# BMS.net
KiCad netlist of a schematic drawn in Altium Designer
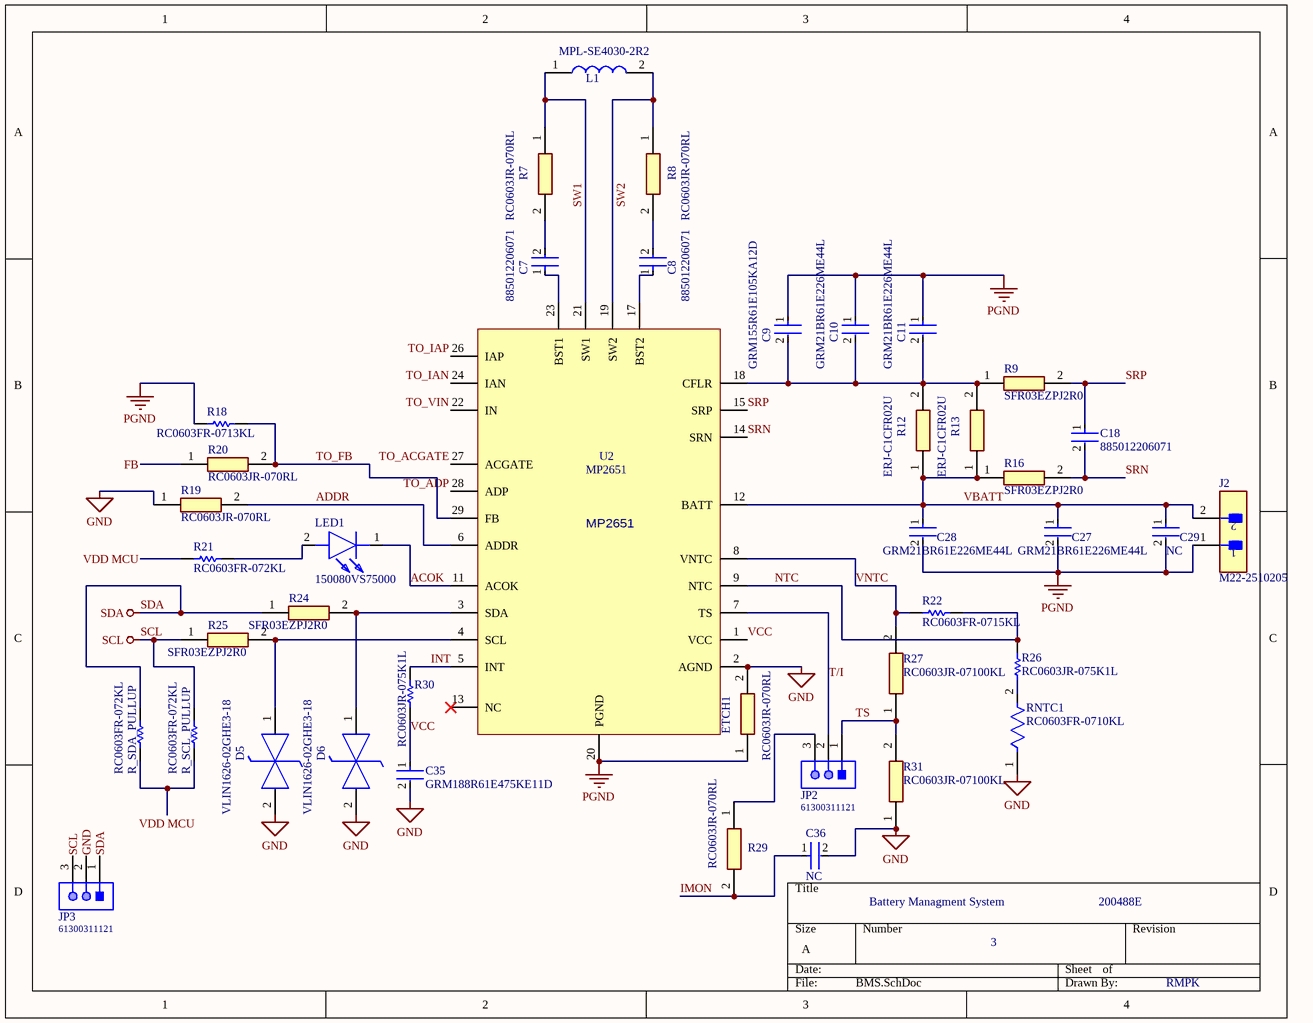
[diagram p0: BMS.SchDoc]

(export (version "E")
  (design (tool "Eeschema 10.0.6"))
  (components
    (comp (ref "C7")
      (value "885012206071")
      (footprint "FP-885012206071-MFG")
      (description "CAP CER 0.1UF 25V X7R 0603")
      (fields (field (name "TOLERANCE") "10%"))
      (libsource (lib "Altium Content Vault") (part "11868f565c42a9108669ba33697ecf6"))
    )
    (comp (ref "C8")
      (value "885012206071")
      (footprint "FP-885012206071-MFG")
      (description "CAP CER 0.1UF 25V X7R 0603")
      (fields (field (name "TOLERANCE") "10%"))
      (libsource (lib "Altium Content Vault") (part "11868f565c42a9108669ba33697ecf6"))
    )
    (comp (ref "C9")
      (value "GRM155R61E105KA12D")
      (footprint "FP-GRM155-0_05-IPC_B")
      (description "Chip Multilayer Ceramic Capacitors for General Purpose, 0402, 1.0uF, X5R, 15%, 10%, 25V")
      (fields (field (name "VOLTAGE") "25V") (field (name "TOLERANCE") "10%"))
      (libsource (lib "Altium Content Vault") (part "02cd4be3c70576c341d710602a673aa"))
    )
    (comp (ref "C10")
      (value "GRM21BR61E226ME44L")
      (footprint "FP-GRM21B-0_2-e0_2_0_7-IPC_B")
      (description "Chip Multilayer Ceramic Capacitors for General Purpose, 0805, 22uF, X5R, 15%, 20%, 25V")
      (fields (field (name "TOLERANCE") "20%") (field (name "VOLTAGE") "25V"))
      (libsource (lib "Altium Content Vault") (part "b4654b650e69147ec39a6b967a45e02"))
    )
    (comp (ref "C11")
      (value "GRM21BR61E226ME44L")
      (footprint "FP-GRM21B-0_2-e0_2_0_7-IPC_B")
      (description "Chip Multilayer Ceramic Capacitors for General Purpose, 0805, 22uF, X5R, 15%, 20%, 25V")
      (fields (field (name "TOLERANCE") "20%") (field (name "VOLTAGE") "25V"))
      (libsource (lib "Altium Content Vault") (part "b4654b650e69147ec39a6b967a45e02"))
    )
    (comp (ref "C18")
      (value "885012206071")
      (footprint "FP-885012206071-MFG")
      (description "CAP CER 0.1UF 25V X7R 0603")
      (fields (field (name "TOLERANCE") "10%"))
      (libsource (lib "Altium Content Vault") (part "11868f565c42a9108669ba33697ecf6"))
    )
    (comp (ref "C27")
      (value "GRM21BR61E226ME44L")
      (footprint "FP-GRM21B-0_2-e0_2_0_7-IPC_B")
      (description "Chip Multilayer Ceramic Capacitors for General Purpose, 0805, 22uF, X5R, 15%, 20%, 25V")
      (fields (field (name "TOLERANCE") "20%") (field (name "VOLTAGE") "25V"))
      (libsource (lib "Altium Content Vault") (part "b4654b650e69147ec39a6b967a45e02"))
    )
    (comp (ref "C28")
      (value "GRM21BR61E226ME44L")
      (footprint "FP-GRM21B-0_2-e0_2_0_7-IPC_B")
      (description "Chip Multilayer Ceramic Capacitors for General Purpose, 0805, 22uF, X5R, 15%, 20%, 25V")
      (fields (field (name "TOLERANCE") "20%") (field (name "VOLTAGE") "25V"))
      (libsource (lib "Altium Content Vault") (part "b4654b650e69147ec39a6b967a45e02"))
    )
    (comp (ref "C29")
      (value "NC")
      (footprint "FP-GRM21B-0_2-e0_2_0_7-IPC_B")
      (description "Chip Multilayer Ceramic Capacitors for General Purpose, 0805, 22uF, X5R, 15%, 20%, 25V")
      (fields (field (name "TOLERANCE") "20%") (field (name "VOLTAGE") "25V"))
      (libsource (lib "Altium Content Vault") (part "b4654b650e69147ec39a6b967a45e02"))
    )
    (comp (ref "C35")
      (value "GRM188R61E475KE11D")
      (footprint "FP-GRM188-0_15-IPC_C")
      (description "Chip Multilayer Ceramic Capacitors for General Purpose, 0603, 4.7uF, X5R, 15%, 10%, 25V")
      (fields (field (name "VOLTAGE") "25V") (field (name "TOLERANCE") "10%"))
      (libsource (lib "Altium Content Vault") (part "02cd4be3c70576c341d710602a673aa"))
    )
    (comp (ref "C36")
      (value "NC")
      (footprint "FP-GRM21B-0_2-e0_2_0_7-IPC_B")
      (description "Chip Multilayer Ceramic Capacitors for General Purpose, 0805, 22uF, X5R, 15%, 20%, 25V")
      (fields (field (name "TOLERANCE") "20%") (field (name "VOLTAGE") "25V"))
      (libsource (lib "Altium Content Vault") (part "b4654b650e69147ec39a6b967a45e02"))
    )
    (comp (ref "D5")
      (value "VLIN1626-02GHE3-18")
      (footprint "SamacSys:SOD2713X115N")
      (description "Diode ESD (Bi-directional)")
      (fields (field (name "MOUSER PART NUMBER") "78-VLIN1626-02GHE318"))
      (libsource (lib "*") (part "VLIN1626-02GHE3-18"))
    )
    (comp (ref "D6")
      (value "VLIN1626-02GHE3-18")
      (footprint "SamacSys:SOD2713X115N")
      (description "Diode ESD (Bi-directional)")
      (fields (field (name "MOUSER PART NUMBER") "78-VLIN1626-02GHE318"))
      (libsource (lib "*") (part "VLIN1626-02GHE3-18"))
    )
    (comp (ref "ETCH1")
      (value "RC0603JR-070RL")
      (footprint "SamacSys:RESC1608X55N")
      (description "Resistor")
      (fields (field (name "MOUSER PART NUMBER") "603-RC0603JR-070RL"))
      (libsource (lib "") (part "RC0603JR-070RL_1"))
    )
    (comp (ref "J2")
      (value "M22-2510205")
      (footprint "FP-M22-2510205-MFG")
      (description "CONN HEADER VERT 2POS 2MM")
      (fields
        (field (name "MANUFACTURER") "Harwin")
        (field (name "OCTOPART") "https://octopart.com/m22-2510205-harwin-2538221")
      )
      (libsource (lib "Altium Content Vault") (part "3bc925449376181038e59eaffc5286c"))
    )
    (comp (ref "JP2")
      (value "61300311121")
      (footprint "61300311121")
      (description "THT Vertical Pin Header WR-PHD, Pitch 2.54 mm, Single Row, 3 pins")
      (fields (field (name "MANUFACTURER") "Wurth Elektronik") (field (name "PUBLISHER") "WurthElektronik"))
      (libsource (lib "Altium Content Vault") (part "WE-CN-1P-M-R3"))
    )
    (comp (ref "JP3")
      (value "61300311121")
      (footprint "61300311121")
      (description "THT Vertical Pin Header WR-PHD, Pitch 2.54 mm, Single Row, 3 pins")
      (fields (field (name "MANUFACTURER") "Wurth Elektronik") (field (name "PUBLISHER") "WurthElektronik"))
      (libsource (lib "Altium Content Vault") (part "WE-CN-1P-M-R3"))
    )
    (comp (ref "L1")
      (value "MPL-SE4030-2R2")
      (footprint "SamacSys:MPLSE40302R2")
      (description "Inductor")
      (fields (field (name "MOUSER PART NUMBER") "946-MPL-SE4030-2R2"))
      (libsource (lib "*") (part "MPL-SE4030-2R2"))
    )
    (comp (ref "LED1")
      (value "150080VS75000")
      (footprint "SamacSys:LEDC2012X80N")
      (description "LED")
      (fields (field (name "MOUSER PART NUMBER") "710-150080VS75000"))
      (libsource (lib "*") (part "150080VS75000"))
    )
    (comp (ref "R7")
      (value "RC0603JR-070RL")
      (footprint "SamacSys:RESC1608X55N")
      (description "Resistor")
      (fields (field (name "MOUSER PART NUMBER") "603-RC0603JR-070RL"))
      (libsource (lib "*") (part "RC0603JR-070RL"))
    )
    (comp (ref "R8")
      (value "RC0603JR-070RL")
      (footprint "SamacSys:RESC1608X55N")
      (description "Resistor")
      (fields (field (name "MOUSER PART NUMBER") "603-RC0603JR-070RL"))
      (libsource (lib "*") (part "RC0603JR-070RL"))
    )
    (comp (ref "R9")
      (value "SFR03EZPJ2R0")
      (footprint "SamacSys:RESC1608X55N")
      (description "Resistor")
      (libsource (lib "*") (part "SFR03EZPJ2R0"))
    )
    (comp (ref "R12")
      (value "ERJ-C1CFR02U")
      (footprint "SamacSys:ERJC1")
      (description "Resistor")
      (fields (field (name "MOUSER PART NUMBER") "667-ERJ-C1CFR02U"))
      (libsource (lib "*") (part "ERJ-C1CFR02U"))
    )
    (comp (ref "R13")
      (value "ERJ-C1CFR02U")
      (footprint "SamacSys:ERJC1")
      (description "Resistor")
      (fields (field (name "MOUSER PART NUMBER") "667-ERJ-C1CFR02U"))
      (libsource (lib "*") (part "ERJ-C1CFR02U"))
    )
    (comp (ref "R16")
      (value "SFR03EZPJ2R0")
      (footprint "SamacSys:RESC1608X55N")
      (description "Resistor")
      (libsource (lib "*") (part "SFR03EZPJ2R0"))
    )
    (comp (ref "R18")
      (value "RC0603FR-0713KL")
      (footprint "RESC1608X55X25LL10T15")
      (description "Chip Resistor, 13 KOhm, +/- 1%, 0.1 W, -55 to 155 degC, 0603 (1608 Metric), RoHS, Tape and Reel")
      (fields (field (name "TOLERANCE") "1%") (field (name "MANUFACTURER") "Yageo"))
      (libsource (lib "Altium Content Vault") (part "RES-2"))
    )
    (comp (ref "R19")
      (value "RC0603JR-070RL")
      (footprint "SamacSys:RESC1608X55N")
      (description "Resistor")
      (fields (field (name "MOUSER PART NUMBER") "603-RC0603JR-070RL"))
      (libsource (lib "") (part "RC0603JR-070RL_2"))
    )
    (comp (ref "R20")
      (value "RC0603JR-070RL")
      (footprint "SamacSys:RESC1608X55N")
      (description "Resistor")
      (fields (field (name "MOUSER PART NUMBER") "603-RC0603JR-070RL"))
      (libsource (lib "") (part "RC0603JR-070RL_2"))
    )
    (comp (ref "R21")
      (value "RC0603FR-072KL")
      (footprint "RESC1608X55X25LL10T15")
      (description "Chip Resistor, 2 KOhm, +/- 1%, 50 V, -55 to 155 degC, 0603 (1608 Metric), RoHS, Tape and Reel")
      (fields (field (name "TOLERANCE") "±1%") (field (name "MANUFACTURER") "Yageo"))
      (libsource (lib "Altium Content Vault") (part "RES-2"))
    )
    (comp (ref "R22")
      (value "RC0603FR-0715KL")
      (footprint "RESC1608X55X25LL10T15")
      (description "Chip Resistor, 15 KOhm, +/- 1%, 0.1 W, -55 to 155 degC, 0603 (1608 Metric), RoHS, Tape and Reel")
      (libsource (lib "Altium Content Vault") (part "RES-2"))
    )
    (comp (ref "R24")
      (value "SFR03EZPJ2R0")
      (footprint "SamacSys:RESC1608X55N")
      (description "Resistor")
      (libsource (lib "*") (part "SFR03EZPJ2R0"))
    )
    (comp (ref "R25")
      (value "SFR03EZPJ2R0")
      (footprint "SamacSys:RESC1608X55N")
      (description "Resistor")
      (libsource (lib "*") (part "SFR03EZPJ2R0"))
    )
    (comp (ref "R26")
      (value "RC0603JR-075K1L")
      (footprint "RESC1608X55X25LL10T15")
      (description "Chip Resistor, 5.1 KOhm, +/- 5%, 0.1 W, -55 to 155 degC, 0603 (1608 Metric), RoHS, Tape and Reel")
      (fields (field (name "TOLERANCE") "5%") (field (name "MANUFACTURER") "Yageo"))
      (libsource (lib "Altium Content Vault") (part "RES-2"))
    )
    (comp (ref "R27")
      (value "RC0603JR-07100KL")
      (footprint "SamacSys:RESC1608X55N")
      (description "Resistor")
      (fields (field (name "MOUSER PART NUMBER") "603-RC0603JR-07100KL"))
      (libsource (lib "*") (part "RC0603JR-07100KL"))
    )
    (comp (ref "R29")
      (value "RC0603JR-070RL")
      (footprint "SamacSys:RESC1608X55N")
      (description "Resistor")
      (fields (field (name "MOUSER PART NUMBER") "603-RC0603JR-070RL"))
      (libsource (lib "*") (part "RC0603JR-070RL"))
    )
    (comp (ref "R30")
      (value "RC0603JR-075K1L")
      (footprint "RESC1608X55X25LL10T15")
      (description "Chip Resistor, 5.1 KOhm, +/- 5%, 0.1 W, -55 to 155 degC, 0603 (1608 Metric), RoHS, Tape and Reel")
      (fields (field (name "TOLERANCE") "5%") (field (name "MANUFACTURER") "Yageo"))
      (libsource (lib "Altium Content Vault") (part "RES-2"))
    )
    (comp (ref "R31")
      (value "RC0603JR-07100KL")
      (footprint "SamacSys:RESC1608X55N")
      (description "Resistor")
      (fields (field (name "MOUSER PART NUMBER") "603-RC0603JR-07100KL"))
      (libsource (lib "*") (part "RC0603JR-07100KL"))
    )
    (comp (ref "RNTC1")
      (value "RC0603FR-0710KL")
      (footprint "FP-RC0603-0_55-IPC_C")
      (description "RES 10K OHM 1% 1/10W 0603")
      (fields (field (name "TOLERANCE") "1%"))
      (libsource (lib "Altium Content Vault") (part "1029c3af85768c4190bb7ad29bc67b5"))
    )
    (comp (ref "R_SCL_PULLUP")
      (value "RC0603FR-072KL")
      (footprint "RESC1608X55X25LL10T15")
      (description "Chip Resistor, 2 KOhm, +/- 1%, 50 V, -55 to 155 degC, 0603 (1608 Metric), RoHS, Tape and Reel")
      (fields (field (name "TOLERANCE") "±1%") (field (name "MANUFACTURER") "Yageo"))
      (libsource (lib "Altium Content Vault") (part "RES-2"))
    )
    (comp (ref "R_SDA_PULLUP")
      (value "RC0603FR-072KL")
      (footprint "RESC1608X55X25LL10T15")
      (description "Chip Resistor, 2 KOhm, +/- 1%, 50 V, -55 to 155 degC, 0603 (1608 Metric), RoHS, Tape and Reel")
      (fields (field (name "TOLERANCE") "±1%") (field (name "MANUFACTURER") "Yageo"))
      (libsource (lib "Altium Content Vault") (part "RES-2"))
    )
    (comp (ref "U2")
      (value "MP2651")
      (footprint "MP2651")
      (description "MP2651 – BUCK-BOOST CHARGER FOR 1 TO 4 CELLS IN SERIES")
      (libsource (lib "Schlib1") (part "MP2651"))
    )
  )
  (nets
    (net (code "1") (name "/ACOK") (class "Default")
      (node (ref "LED1") (pin "1") (pinfunction "K_1") (pintype "passive"))
      (node (ref "U2") (pin "11") (pinfunction "ACOK_11") (pintype "passive"))
    )
    (net (code "2") (name "/ADDR") (class "Default")
      (node (ref "R19") (pin "2") (pinfunction "2_2") (pintype "passive"))
      (node (ref "U2") (pin "6") (pinfunction "ADDR_6") (pintype "passive"))
    )
    (net (code "3") (name "/FB") (class "Default")
      (node (ref "R20") (pin "1") (pinfunction "1_1") (pintype "passive"))
    )
    (net (code "4") (name "/IMON") (class "Default")
      (node (ref "C36") (pin "1") (pinfunction "1_1") (pintype "passive"))
      (node (ref "R29") (pin "2") (pinfunction "2_2") (pintype "passive"))
    )
    (net (code "5") (name "/INT") (class "Default")
      (node (ref "R30") (pin "2") (pinfunction "2_2") (pintype "passive"))
      (node (ref "U2") (pin "5") (pinfunction "INT_5") (pintype "passive"))
    )
    (net (code "6") (name "/NTC") (class "Default")
      (node (ref "R22") (pin "2") (pinfunction "2_2") (pintype "passive"))
      (node (ref "R26") (pin "2") (pinfunction "2_2") (pintype "passive"))
      (node (ref "U2") (pin "9") (pinfunction "NTC_9") (pintype "passive"))
    )
    (net (code "7") (name "/SRN") (class "Default")
      (node (ref "C18") (pin "2") (pinfunction "2_2") (pintype "passive"))
      (node (ref "R16") (pin "2") (pinfunction "2_2") (pintype "passive"))
      (node (ref "U2") (pin "14") (pinfunction "SRN_14") (pintype "passive"))
    )
    (net (code "8") (name "/SRP") (class "Default")
      (node (ref "C18") (pin "1") (pinfunction "1_1") (pintype "passive"))
      (node (ref "R9") (pin "2") (pinfunction "2_2") (pintype "passive"))
      (node (ref "U2") (pin "15") (pinfunction "SRP_15") (pintype "passive"))
    )
    (net (code "9") (name "/SW1") (class "Default")
      (node (ref "L1") (pin "1") (pinfunction "1_1") (pintype "passive"))
      (node (ref "R7") (pin "1") (pinfunction "1_1") (pintype "passive"))
      (node (ref "U2") (pin "21") (pinfunction "SW1_21") (pintype "passive"))
    )
    (net (code "10") (name "/SW2") (class "Default")
      (node (ref "L1") (pin "2") (pinfunction "2_2") (pintype "passive"))
      (node (ref "R8") (pin "1") (pinfunction "1_1") (pintype "passive"))
      (node (ref "U2") (pin "19") (pinfunction "SW2_19") (pintype "passive"))
    )
    (net (code "11") (name "/TO_ACGATE") (class "Default")
      (node (ref "U2") (pin "27") (pinfunction "ACGATE_27") (pintype "passive"))
    )
    (net (code "12") (name "/TO_ADP") (class "Default")
      (node (ref "U2") (pin "28") (pinfunction "ADP_28") (pintype "passive"))
    )
    (net (code "13") (name "/TO_FB") (class "Default")
      (node (ref "R18") (pin "2") (pinfunction "2_2") (pintype "passive"))
      (node (ref "R20") (pin "2") (pinfunction "2_2") (pintype "passive"))
      (node (ref "U2") (pin "29") (pinfunction "FB_29") (pintype "passive"))
    )
    (net (code "14") (name "/TO_IAN") (class "Default")
      (node (ref "U2") (pin "24") (pinfunction "IAN_24") (pintype "passive"))
    )
    (net (code "15") (name "/TO_IAP") (class "Default")
      (node (ref "U2") (pin "26") (pinfunction "IAP_26") (pintype "passive"))
    )
    (net (code "16") (name "/TO_VIN") (class "Default")
      (node (ref "U2") (pin "22") (pinfunction "IN_22") (pintype "passive"))
    )
    (net (code "17") (name "/TS") (class "Default")
      (node (ref "JP2") (pin "1") (pinfunction "1_1") (pintype "passive"))
      (node (ref "R27") (pin "1") (pinfunction "1_1") (pintype "passive"))
      (node (ref "R31") (pin "2") (pinfunction "2_2") (pintype "passive"))
    )
    (net (code "18") (name "/T{slash}I") (class "Default")
      (node (ref "JP2") (pin "2") (pinfunction "2_2") (pintype "passive"))
      (node (ref "U2") (pin "7") (pinfunction "TS_7") (pintype "passive"))
    )
    (net (code "19") (name "/VBATT") (class "Default")
      (node (ref "C27") (pin "1") (pinfunction "1_1") (pintype "passive"))
      (node (ref "C28") (pin "1") (pinfunction "1_1") (pintype "passive"))
      (node (ref "C29") (pin "1") (pinfunction "1_1") (pintype "passive"))
      (node (ref "J2") (pin "2") (pinfunction "2_2") (pintype "passive"))
      (node (ref "R12") (pin "1") (pinfunction "1_1") (pintype "passive"))
      (node (ref "R13") (pin "1") (pinfunction "1_1") (pintype "passive"))
      (node (ref "R16") (pin "1") (pinfunction "1_1") (pintype "passive"))
      (node (ref "U2") (pin "12") (pinfunction "BATT_12") (pintype "passive"))
    )
    (net (code "20") (name "/VCC") (class "Default")
      (node (ref "C35") (pin "1") (pinfunction "1_1") (pintype "passive"))
      (node (ref "R30") (pin "1") (pinfunction "1_1") (pintype "passive"))
      (node (ref "U2") (pin "1") (pinfunction "VCC_1") (pintype "passive"))
    )
    (net (code "21") (name "/VDD MCU") (class "Default")
      (node (ref "R21") (pin "1") (pinfunction "1_1") (pintype "passive"))
      (node (ref "R_SCL_PULLUP") (pin "1") (pinfunction "1_1") (pintype "passive"))
      (node (ref "R_SDA_PULLUP") (pin "1") (pinfunction "1_1") (pintype "passive"))
    )
    (net (code "22") (name "/VNTC") (class "Default")
      (node (ref "R22") (pin "1") (pinfunction "1_1") (pintype "passive"))
      (node (ref "R27") (pin "2") (pinfunction "2_2") (pintype "passive"))
      (node (ref "U2") (pin "8") (pinfunction "VNTC_8") (pintype "passive"))
    )
    (net (code "23") (name "GND") (class "Default")
      (node (ref "C35") (pin "2") (pinfunction "2_2") (pintype "passive"))
      (node (ref "C36") (pin "2") (pinfunction "2_2") (pintype "passive"))
      (node (ref "D5") (pin "2") (pinfunction "K2_2") (pintype "passive"))
      (node (ref "D6") (pin "2") (pinfunction "K2_2") (pintype "passive"))
      (node (ref "ETCH1") (pin "2") (pinfunction "2_2") (pintype "passive"))
      (node (ref "JP3") (pin "2") (pinfunction "2_2") (pintype "passive"))
      (node (ref "R19") (pin "1") (pinfunction "1_1") (pintype "passive"))
      (node (ref "R31") (pin "1") (pinfunction "1_1") (pintype "passive"))
      (node (ref "RNTC1") (pin "1") (pinfunction "1_1") (pintype "passive"))
      (node (ref "U2") (pin "2") (pinfunction "AGND_2") (pintype "passive"))
    )
    (net (code "24") (name "Net-(C7-Pad2)") (class "Default")
      (node (ref "C7") (pin "2") (pinfunction "2_2") (pintype "passive"))
      (node (ref "R7") (pin "2") (pinfunction "2_2") (pintype "passive"))
    )
    (net (code "25") (name "Net-(C8-Pad2)") (class "Default")
      (node (ref "C8") (pin "2") (pinfunction "2_2") (pintype "passive"))
      (node (ref "R8") (pin "2") (pinfunction "2_2") (pintype "passive"))
    )
    (net (code "26") (name "Net-(D5-K1)") (class "Default")
      (node (ref "D5") (pin "1") (pinfunction "K1_1") (pintype "passive"))
      (node (ref "R25") (pin "2") (pinfunction "2_2") (pintype "passive"))
      (node (ref "U2") (pin "4") (pinfunction "SCL_4") (pintype "passive"))
    )
    (net (code "27") (name "Net-(D6-K1)") (class "Default")
      (node (ref "D6") (pin "1") (pinfunction "K1_1") (pintype "passive"))
      (node (ref "R24") (pin "2") (pinfunction "2_2") (pintype "passive"))
      (node (ref "U2") (pin "3") (pinfunction "SDA_3") (pintype "passive"))
    )
    (net (code "28") (name "Net-(JP2-Pad3)") (class "Default")
      (node (ref "JP2") (pin "3") (pinfunction "3_3") (pintype "passive"))
      (node (ref "R29") (pin "1") (pinfunction "1_1") (pintype "passive"))
    )
    (net (code "29") (name "Net-(LED1-A)") (class "Default")
      (node (ref "LED1") (pin "2") (pinfunction "A_2") (pintype "passive"))
      (node (ref "R21") (pin "2") (pinfunction "2_2") (pintype "passive"))
    )
    (net (code "30") (name "Net-(R26-Pad1)") (class "Default")
      (node (ref "R26") (pin "1") (pinfunction "1_1") (pintype "passive"))
      (node (ref "RNTC1") (pin "2") (pinfunction "2_2") (pintype "passive"))
    )
    (net (code "31") (name "Net-(U2-BST1)") (class "Default")
      (node (ref "C7") (pin "1") (pinfunction "1_1") (pintype "passive"))
      (node (ref "U2") (pin "23") (pinfunction "BST1_23") (pintype "passive"))
    )
    (net (code "32") (name "Net-(U2-BST2)") (class "Default")
      (node (ref "C8") (pin "1") (pinfunction "1_1") (pintype "passive"))
      (node (ref "U2") (pin "17") (pinfunction "BST2_17") (pintype "passive"))
    )
    (net (code "33") (name "Net-(U2-CFLR)") (class "Default")
      (node (ref "C10") (pin "2") (pinfunction "2_2") (pintype "passive"))
      (node (ref "C11") (pin "2") (pinfunction "2_2") (pintype "passive"))
      (node (ref "C9") (pin "2") (pinfunction "2_2") (pintype "passive"))
      (node (ref "R12") (pin "2") (pinfunction "2_2") (pintype "passive"))
      (node (ref "R13") (pin "2") (pinfunction "2_2") (pintype "passive"))
      (node (ref "R9") (pin "1") (pinfunction "1_1") (pintype "passive"))
      (node (ref "U2") (pin "18") (pinfunction "CFLR_18") (pintype "passive"))
    )
    (net (code "34") (name "PGND") (class "Default")
      (node (ref "C10") (pin "1") (pinfunction "1_1") (pintype "passive"))
      (node (ref "C11") (pin "1") (pinfunction "1_1") (pintype "passive"))
      (node (ref "C27") (pin "2") (pinfunction "2_2") (pintype "passive"))
      (node (ref "C28") (pin "2") (pinfunction "2_2") (pintype "passive"))
      (node (ref "C29") (pin "2") (pinfunction "2_2") (pintype "passive"))
      (node (ref "C9") (pin "1") (pinfunction "1_1") (pintype "passive"))
      (node (ref "ETCH1") (pin "1") (pinfunction "1_1") (pintype "passive"))
      (node (ref "J2") (pin "1") (pinfunction "1_1") (pintype "passive"))
      (node (ref "R18") (pin "1") (pinfunction "1_1") (pintype "passive"))
      (node (ref "U2") (pin "20") (pinfunction "PGND_20") (pintype "passive"))
    )
    (net (code "35") (name "SCL") (class "Default")
      (node (ref "JP3") (pin "3") (pinfunction "3_3") (pintype "passive"))
      (node (ref "R25") (pin "1") (pinfunction "1_1") (pintype "passive"))
      (node (ref "R_SCL_PULLUP") (pin "2") (pinfunction "2_2") (pintype "passive"))
    )
    (net (code "36") (name "SDA") (class "Default")
      (node (ref "JP3") (pin "1") (pinfunction "1_1") (pintype "passive"))
      (node (ref "R24") (pin "1") (pinfunction "1_1") (pintype "passive"))
      (node (ref "R_SDA_PULLUP") (pin "2") (pinfunction "2_2") (pintype "passive"))
    )
    (net (code "37") (name "unconnected-(U2-NC-Pad13)") (class "Default")
      (node (ref "U2") (pin "13") (pinfunction "NC_13") (pintype "passive+no_connect"))
    )
  )
)
